# BARC_mounting_circuitry.net
KiCad netlist of a schematic drawn in Altium Designer
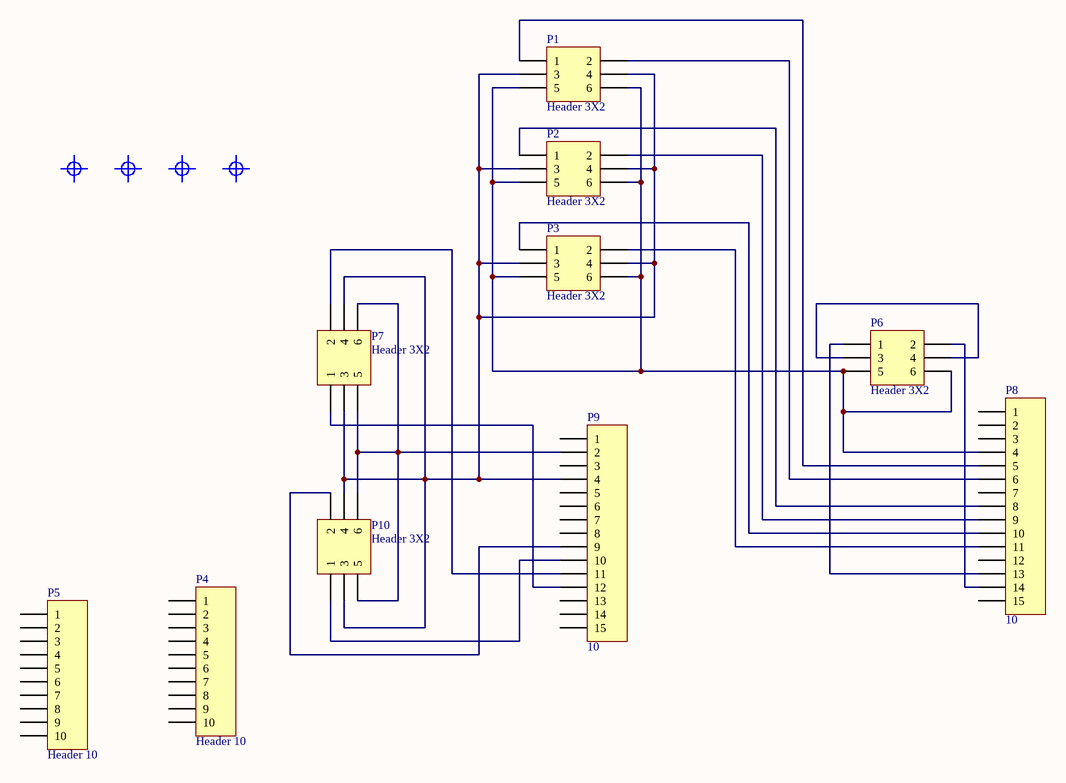
[diagram p0: BARC_mounting_circuitry.SchDoc]

(export (version "E")
  (design (tool "Eeschema 10.0.6"))
  (components
    (comp (ref "MP1")
      (value "Mounting hole M2")
      (footprint "mh_m2")
      (description "Hole for M2 srews")
      (libsource (lib "IDSC MechanicalParts") (part "Mounting hole M2"))
    )
    (comp (ref "MP2")
      (value "Mounting hole M2")
      (footprint "mh_m2")
      (description "Hole for M2 srews")
      (libsource (lib "IDSC MechanicalParts") (part "Mounting hole M2"))
    )
    (comp (ref "MP3")
      (value "Mounting hole M2")
      (footprint "mh_m2")
      (description "Hole for M2 srews")
      (libsource (lib "IDSC MechanicalParts") (part "Mounting hole M2"))
    )
    (comp (ref "MP4")
      (value "Mounting hole M2")
      (footprint "mh_m2")
      (description "Hole for M2 srews")
      (libsource (lib "IDSC MechanicalParts") (part "Mounting hole M2"))
    )
    (comp (ref "P1")
      (value "Header 3X2")
      (footprint "HDR2X3")
      (description "Header, 3-Pin, Dual row")
      (libsource (lib "IDSC std connectors") (part "Header 3X2"))
    )
    (comp (ref "P2")
      (value "Header 3X2")
      (footprint "HDR2X3")
      (description "Header, 3-Pin, Dual row")
      (libsource (lib "IDSC std connectors") (part "Header 3X2"))
    )
    (comp (ref "P3")
      (value "Header 3X2")
      (footprint "HDR2X3")
      (description "Header, 3-Pin, Dual row")
      (libsource (lib "IDSC std connectors") (part "Header 3X2"))
    )
    (comp (ref "P4")
      (value "Header 10")
      (footprint "HDR1X10")
      (description "Header, 10-Pin")
      (fields (field (name "PUBLISHER") "Altium Limited"))
      (libsource (lib "Miscellaneous Connectors") (part "Header 10"))
    )
    (comp (ref "P5")
      (value "Header 10")
      (footprint "HDR1X10")
      (description "Header, 10-Pin")
      (fields (field (name "PUBLISHER") "Altium Limited"))
      (libsource (lib "Miscellaneous Connectors") (part "Header 10"))
    )
    (comp (ref "P6")
      (value "Header 3X2")
      (footprint "HDR2X3")
      (description "Header, 3-Pin, Dual row")
      (libsource (lib "IDSC std connectors") (part "Header 3X2"))
    )
    (comp (ref "P7")
      (value "Header 3X2")
      (footprint "HDR2X3")
      (description "Header, 3-Pin, Dual row")
      (libsource (lib "") (part "Header 3X2_1"))
    )
    (comp (ref "P8")
      (value "10")
      (footprint "HDR1X15")
      (description "Header, 15-Pin")
      (libsource (lib "IDSC std connectors") (part "Header 15"))
    )
    (comp (ref "P9")
      (value "10")
      (footprint "HDR1X15")
      (description "Header, 15-Pin")
      (libsource (lib "IDSC std connectors") (part "Header 15"))
    )
    (comp (ref "P10")
      (value "Header 3X2")
      (footprint "HDR2X3")
      (description "Header, 3-Pin, Dual row")
      (libsource (lib "") (part "Header 3X2_1"))
    )
  )
  (nets
    (net (code "1") (name "Net-(P1-Pad1)") (class "Default")
      (node (ref "P1") (pin "1") (pinfunction "1_1") (pintype "passive"))
      (node (ref "P8") (pin "5") (pinfunction "5_5") (pintype "passive"))
    )
    (net (code "2") (name "Net-(P1-Pad2)") (class "Default")
      (node (ref "P1") (pin "2") (pinfunction "2_2") (pintype "passive"))
      (node (ref "P8") (pin "6") (pinfunction "6_6") (pintype "passive"))
    )
    (net (code "3") (name "Net-(P1-Pad3)") (class "Default")
      (node (ref "P1") (pin "3") (pinfunction "3_3") (pintype "passive"))
      (node (ref "P1") (pin "4") (pinfunction "4_4") (pintype "passive"))
      (node (ref "P10") (pin "3") (pinfunction "3_3") (pintype "passive"))
      (node (ref "P10") (pin "4") (pinfunction "4_4") (pintype "passive"))
      (node (ref "P2") (pin "3") (pinfunction "3_3") (pintype "passive"))
      (node (ref "P2") (pin "4") (pinfunction "4_4") (pintype "passive"))
      (node (ref "P3") (pin "3") (pinfunction "3_3") (pintype "passive"))
      (node (ref "P3") (pin "4") (pinfunction "4_4") (pintype "passive"))
      (node (ref "P7") (pin "3") (pinfunction "3_3") (pintype "passive"))
      (node (ref "P7") (pin "4") (pinfunction "4_4") (pintype "passive"))
      (node (ref "P9") (pin "4") (pinfunction "4_4") (pintype "passive"))
    )
    (net (code "4") (name "Net-(P1-Pad5)") (class "Default")
      (node (ref "P1") (pin "5") (pinfunction "5_5") (pintype "passive"))
      (node (ref "P1") (pin "6") (pinfunction "6_6") (pintype "passive"))
      (node (ref "P2") (pin "5") (pinfunction "5_5") (pintype "passive"))
      (node (ref "P2") (pin "6") (pinfunction "6_6") (pintype "passive"))
      (node (ref "P3") (pin "5") (pinfunction "5_5") (pintype "passive"))
      (node (ref "P3") (pin "6") (pinfunction "6_6") (pintype "passive"))
      (node (ref "P6") (pin "5") (pinfunction "5_5") (pintype "passive"))
      (node (ref "P6") (pin "6") (pinfunction "6_6") (pintype "passive"))
      (node (ref "P8") (pin "4") (pinfunction "4_4") (pintype "passive"))
    )
    (net (code "5") (name "Net-(P2-Pad1)") (class "Default")
      (node (ref "P2") (pin "1") (pinfunction "1_1") (pintype "passive"))
      (node (ref "P8") (pin "8") (pinfunction "8_8") (pintype "passive"))
    )
    (net (code "6") (name "Net-(P2-Pad2)") (class "Default")
      (node (ref "P2") (pin "2") (pinfunction "2_2") (pintype "passive"))
      (node (ref "P8") (pin "9") (pinfunction "9_9") (pintype "passive"))
    )
    (net (code "7") (name "Net-(P3-Pad1)") (class "Default")
      (node (ref "P3") (pin "1") (pinfunction "1_1") (pintype "passive"))
      (node (ref "P8") (pin "10") (pinfunction "10_10") (pintype "passive"))
    )
    (net (code "8") (name "Net-(P3-Pad2)") (class "Default")
      (node (ref "P3") (pin "2") (pinfunction "2_2") (pintype "passive"))
      (node (ref "P8") (pin "11") (pinfunction "11_11") (pintype "passive"))
    )
    (net (code "9") (name "Net-(P6-Pad1)") (class "Default")
      (node (ref "P6") (pin "1") (pinfunction "1_1") (pintype "passive"))
      (node (ref "P8") (pin "13") (pinfunction "13_13") (pintype "passive"))
    )
    (net (code "10") (name "Net-(P6-Pad2)") (class "Default")
      (node (ref "P6") (pin "2") (pinfunction "2_2") (pintype "passive"))
      (node (ref "P8") (pin "14") (pinfunction "14_14") (pintype "passive"))
    )
    (net (code "11") (name "Net-(P6-Pad3)") (class "Default")
      (node (ref "P6") (pin "3") (pinfunction "3_3") (pintype "passive"))
      (node (ref "P6") (pin "4") (pinfunction "4_4") (pintype "passive"))
    )
    (net (code "12") (name "Net-(P7-Pad1)") (class "Default")
      (node (ref "P7") (pin "1") (pinfunction "1_1") (pintype "passive"))
      (node (ref "P9") (pin "12") (pinfunction "12_12") (pintype "passive"))
    )
    (net (code "13") (name "Net-(P7-Pad2)") (class "Default")
      (node (ref "P7") (pin "2") (pinfunction "2_2") (pintype "passive"))
      (node (ref "P9") (pin "11") (pinfunction "11_11") (pintype "passive"))
    )
    (net (code "14") (name "Net-(P10-Pad1)") (class "Default")
      (node (ref "P10") (pin "1") (pinfunction "1_1") (pintype "passive"))
      (node (ref "P9") (pin "10") (pinfunction "10_10") (pintype "passive"))
    )
    (net (code "15") (name "Net-(P10-Pad2)") (class "Default")
      (node (ref "P10") (pin "2") (pinfunction "2_2") (pintype "passive"))
      (node (ref "P9") (pin "9") (pinfunction "9_9") (pintype "passive"))
    )
    (net (code "16") (name "Net-(P10-Pad5)") (class "Default")
      (node (ref "P10") (pin "5") (pinfunction "5_5") (pintype "passive"))
      (node (ref "P10") (pin "6") (pinfunction "6_6") (pintype "passive"))
      (node (ref "P7") (pin "5") (pinfunction "5_5") (pintype "passive"))
      (node (ref "P7") (pin "6") (pinfunction "6_6") (pintype "passive"))
      (node (ref "P9") (pin "2") (pinfunction "2_2") (pintype "passive"))
    )
    (net (code "17") (name "unconnected-(P4-Pad1)") (class "Default")
      (node (ref "P4") (pin "1") (pinfunction "1_1") (pintype "passive"))
    )
    (net (code "18") (name "unconnected-(P4-Pad2)") (class "Default")
      (node (ref "P4") (pin "2") (pinfunction "2_2") (pintype "passive"))
    )
    (net (code "19") (name "unconnected-(P4-Pad3)") (class "Default")
      (node (ref "P4") (pin "3") (pinfunction "3_3") (pintype "passive"))
    )
    (net (code "20") (name "unconnected-(P4-Pad4)") (class "Default")
      (node (ref "P4") (pin "4") (pinfunction "4_4") (pintype "passive"))
    )
    (net (code "21") (name "unconnected-(P4-Pad5)") (class "Default")
      (node (ref "P4") (pin "5") (pinfunction "5_5") (pintype "passive"))
    )
    (net (code "22") (name "unconnected-(P4-Pad6)") (class "Default")
      (node (ref "P4") (pin "6") (pinfunction "6_6") (pintype "passive"))
    )
    (net (code "23") (name "unconnected-(P4-Pad7)") (class "Default")
      (node (ref "P4") (pin "7") (pinfunction "7_7") (pintype "passive"))
    )
    (net (code "24") (name "unconnected-(P4-Pad8)") (class "Default")
      (node (ref "P4") (pin "8") (pinfunction "8_8") (pintype "passive"))
    )
    (net (code "25") (name "unconnected-(P4-Pad9)") (class "Default")
      (node (ref "P4") (pin "9") (pinfunction "9_9") (pintype "passive"))
    )
    (net (code "26") (name "unconnected-(P4-Pad10)") (class "Default")
      (node (ref "P4") (pin "10") (pinfunction "10_10") (pintype "passive"))
    )
    (net (code "27") (name "unconnected-(P5-Pad1)") (class "Default")
      (node (ref "P5") (pin "1") (pinfunction "1_1") (pintype "passive"))
    )
    (net (code "28") (name "unconnected-(P5-Pad2)") (class "Default")
      (node (ref "P5") (pin "2") (pinfunction "2_2") (pintype "passive"))
    )
    (net (code "29") (name "unconnected-(P5-Pad3)") (class "Default")
      (node (ref "P5") (pin "3") (pinfunction "3_3") (pintype "passive"))
    )
    (net (code "30") (name "unconnected-(P5-Pad4)") (class "Default")
      (node (ref "P5") (pin "4") (pinfunction "4_4") (pintype "passive"))
    )
    (net (code "31") (name "unconnected-(P5-Pad5)") (class "Default")
      (node (ref "P5") (pin "5") (pinfunction "5_5") (pintype "passive"))
    )
    (net (code "32") (name "unconnected-(P5-Pad6)") (class "Default")
      (node (ref "P5") (pin "6") (pinfunction "6_6") (pintype "passive"))
    )
    (net (code "33") (name "unconnected-(P5-Pad7)") (class "Default")
      (node (ref "P5") (pin "7") (pinfunction "7_7") (pintype "passive"))
    )
    (net (code "34") (name "unconnected-(P5-Pad8)") (class "Default")
      (node (ref "P5") (pin "8") (pinfunction "8_8") (pintype "passive"))
    )
    (net (code "35") (name "unconnected-(P5-Pad9)") (class "Default")
      (node (ref "P5") (pin "9") (pinfunction "9_9") (pintype "passive"))
    )
    (net (code "36") (name "unconnected-(P5-Pad10)") (class "Default")
      (node (ref "P5") (pin "10") (pinfunction "10_10") (pintype "passive"))
    )
    (net (code "37") (name "unconnected-(P8-Pad1)") (class "Default")
      (node (ref "P8") (pin "1") (pinfunction "1_1") (pintype "passive"))
    )
    (net (code "38") (name "unconnected-(P8-Pad2)") (class "Default")
      (node (ref "P8") (pin "2") (pinfunction "2_2") (pintype "passive"))
    )
    (net (code "39") (name "unconnected-(P8-Pad3)") (class "Default")
      (node (ref "P8") (pin "3") (pinfunction "3_3") (pintype "passive"))
    )
    (net (code "40") (name "unconnected-(P8-Pad7)") (class "Default")
      (node (ref "P8") (pin "7") (pinfunction "7_7") (pintype "passive"))
    )
    (net (code "41") (name "unconnected-(P8-Pad12)") (class "Default")
      (node (ref "P8") (pin "12") (pinfunction "12_12") (pintype "passive"))
    )
    (net (code "42") (name "unconnected-(P8-Pad15)") (class "Default")
      (node (ref "P8") (pin "15") (pinfunction "15_15") (pintype "passive"))
    )
    (net (code "43") (name "unconnected-(P9-Pad1)") (class "Default")
      (node (ref "P9") (pin "1") (pinfunction "1_1") (pintype "passive"))
    )
    (net (code "44") (name "unconnected-(P9-Pad3)") (class "Default")
      (node (ref "P9") (pin "3") (pinfunction "3_3") (pintype "passive"))
    )
    (net (code "45") (name "unconnected-(P9-Pad5)") (class "Default")
      (node (ref "P9") (pin "5") (pinfunction "5_5") (pintype "passive"))
    )
    (net (code "46") (name "unconnected-(P9-Pad6)") (class "Default")
      (node (ref "P9") (pin "6") (pinfunction "6_6") (pintype "passive"))
    )
    (net (code "47") (name "unconnected-(P9-Pad7)") (class "Default")
      (node (ref "P9") (pin "7") (pinfunction "7_7") (pintype "passive"))
    )
    (net (code "48") (name "unconnected-(P9-Pad8)") (class "Default")
      (node (ref "P9") (pin "8") (pinfunction "8_8") (pintype "passive"))
    )
    (net (code "49") (name "unconnected-(P9-Pad13)") (class "Default")
      (node (ref "P9") (pin "13") (pinfunction "13_13") (pintype "passive"))
    )
    (net (code "50") (name "unconnected-(P9-Pad14)") (class "Default")
      (node (ref "P9") (pin "14") (pinfunction "14_14") (pintype "passive"))
    )
    (net (code "51") (name "unconnected-(P9-Pad15)") (class "Default")
      (node (ref "P9") (pin "15") (pinfunction "15_15") (pintype "passive"))
    )
  )
)
